# core_pwr.net
KiCad netlist of a schematic drawn in Altium Designer
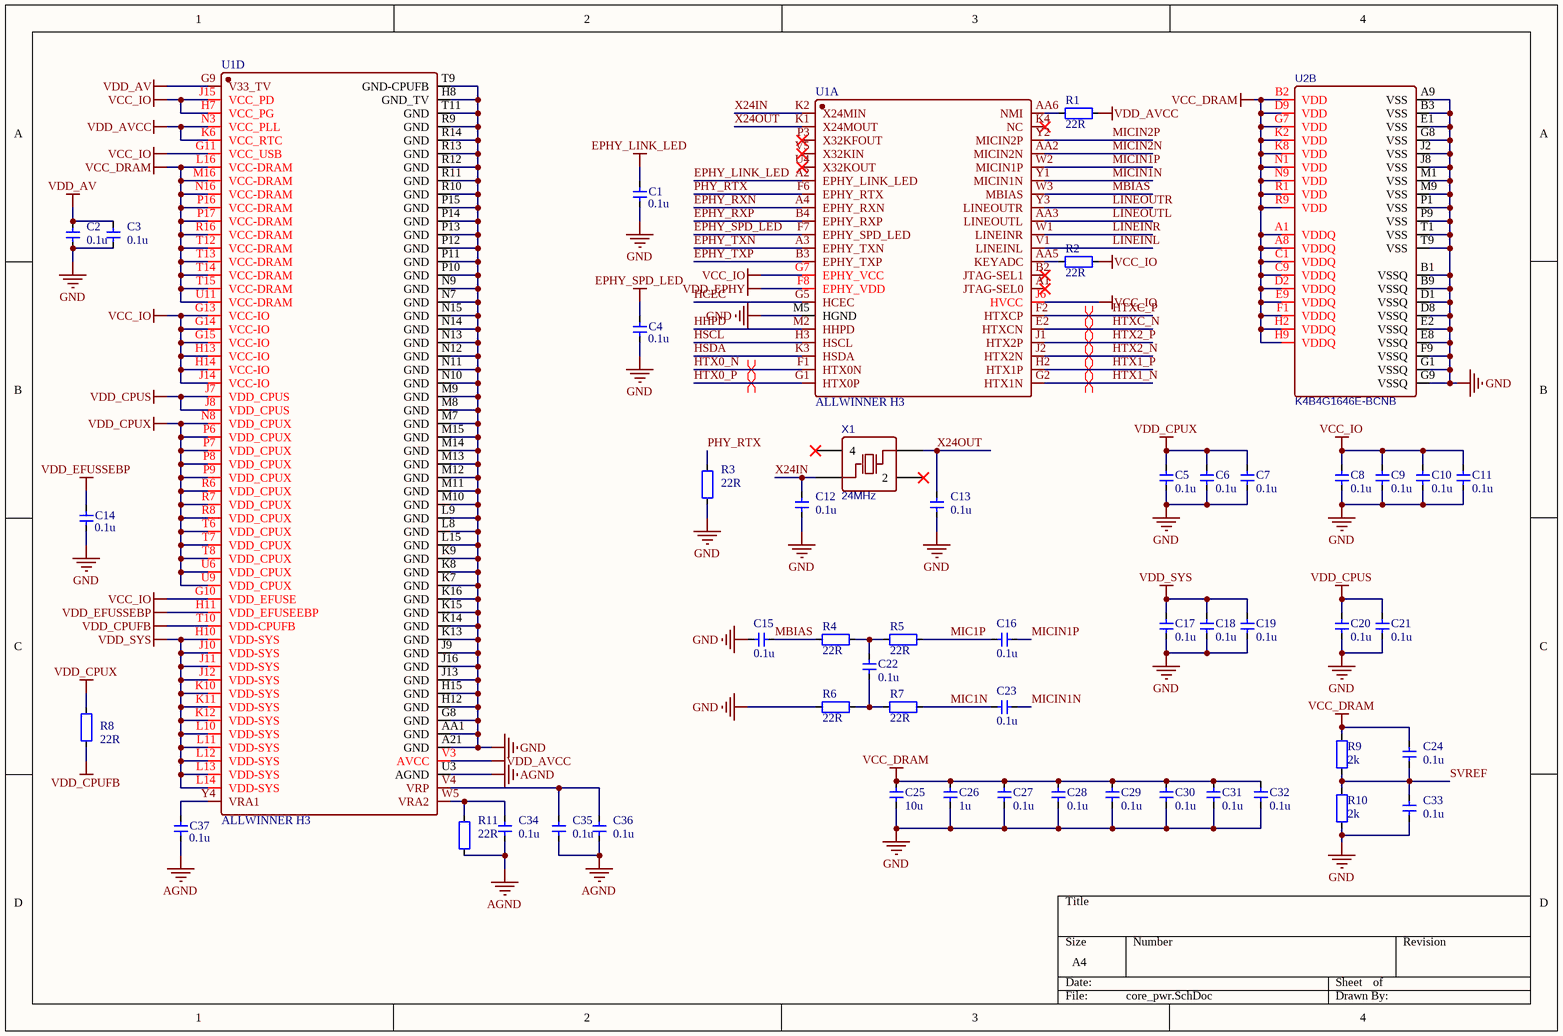
[diagram p0: core_pwr.SchDoc]

(export (version "E")
  (design (tool "Eeschema 10.0.6"))
  (components
    (comp (ref "C1")
      (value "0.1u")
      (footprint "C0402")
      (description "Capacitor")
      (fields (field (name "Comment") "CAP-0402"))
      (libsource (lib "core") (part "CAP-0402"))
    )
    (comp (ref "C2")
      (value "0.1u")
      (footprint "C0402")
      (description "Capacitor")
      (fields (field (name "Comment") "CAP-0402"))
      (libsource (lib "core") (part "CAP-0402"))
    )
    (comp (ref "C3")
      (value "0.1u")
      (footprint "C0402")
      (description "Capacitor")
      (fields (field (name "Comment") "CAP-0402"))
      (libsource (lib "core") (part "CAP-0402"))
    )
    (comp (ref "C4")
      (value "0.1u")
      (footprint "C0402")
      (description "Capacitor")
      (fields (field (name "Comment") "CAP-0402"))
      (libsource (lib "core") (part "CAP-0402"))
    )
    (comp (ref "C5")
      (value "0.1u")
      (footprint "C0402")
      (description "Capacitor")
      (fields (field (name "Comment") "CAP-0402"))
      (libsource (lib "core") (part "CAP-0402"))
    )
    (comp (ref "C6")
      (value "0.1u")
      (footprint "C0402")
      (description "Capacitor")
      (fields (field (name "Comment") "CAP-0402"))
      (libsource (lib "core") (part "CAP-0402"))
    )
    (comp (ref "C7")
      (value "0.1u")
      (footprint "C0402")
      (description "Capacitor")
      (fields (field (name "Comment") "CAP-0402"))
      (libsource (lib "core") (part "CAP-0402"))
    )
    (comp (ref "C8")
      (value "0.1u")
      (footprint "C0402")
      (description "Capacitor")
      (fields (field (name "Comment") "CAP-0402"))
      (libsource (lib "core") (part "CAP-0402"))
    )
    (comp (ref "C9")
      (value "0.1u")
      (footprint "C0402")
      (description "Capacitor")
      (fields (field (name "Comment") "CAP-0402"))
      (libsource (lib "core") (part "CAP-0402"))
    )
    (comp (ref "C10")
      (value "0.1u")
      (footprint "C0402")
      (description "Capacitor")
      (fields (field (name "Comment") "CAP-0402"))
      (libsource (lib "core") (part "CAP-0402"))
    )
    (comp (ref "C11")
      (value "0.1u")
      (footprint "C0402")
      (description "Capacitor")
      (fields (field (name "Comment") "CAP-0402"))
      (libsource (lib "core") (part "CAP-0402"))
    )
    (comp (ref "C12")
      (value "0.1u")
      (footprint "C0402")
      (description "Capacitor")
      (fields (field (name "Comment") "CAP-0402"))
      (libsource (lib "core") (part "CAP-0402"))
    )
    (comp (ref "C13")
      (value "0.1u")
      (footprint "C0402")
      (description "Capacitor")
      (fields (field (name "Comment") "CAP-0402"))
      (libsource (lib "core") (part "CAP-0402"))
    )
    (comp (ref "C14")
      (value "0.1u")
      (footprint "C0402")
      (description "Capacitor")
      (fields (field (name "Comment") "CAP-0402"))
      (libsource (lib "core") (part "CAP-0402"))
    )
    (comp (ref "C15")
      (value "0.1u")
      (footprint "C0402")
      (description "Capacitor")
      (fields (field (name "Comment") "CAP-0402"))
      (libsource (lib "core") (part "CAP-0402"))
    )
    (comp (ref "C16")
      (value "0.1u")
      (footprint "C0402")
      (description "Capacitor")
      (fields (field (name "Comment") "CAP-0402"))
      (libsource (lib "core") (part "CAP-0402"))
    )
    (comp (ref "C17")
      (value "0.1u")
      (footprint "C0402")
      (description "Capacitor")
      (fields (field (name "Comment") "CAP-0402"))
      (libsource (lib "core") (part "CAP-0402"))
    )
    (comp (ref "C18")
      (value "0.1u")
      (footprint "C0402")
      (description "Capacitor")
      (fields (field (name "Comment") "CAP-0402"))
      (libsource (lib "core") (part "CAP-0402"))
    )
    (comp (ref "C19")
      (value "0.1u")
      (footprint "C0402")
      (description "Capacitor")
      (fields (field (name "Comment") "CAP-0402"))
      (libsource (lib "core") (part "CAP-0402"))
    )
    (comp (ref "C20")
      (value "0.1u")
      (footprint "C0402")
      (description "Capacitor")
      (fields (field (name "Comment") "CAP-0402"))
      (libsource (lib "core") (part "CAP-0402"))
    )
    (comp (ref "C21")
      (value "0.1u")
      (footprint "C0402")
      (description "Capacitor")
      (fields (field (name "Comment") "CAP-0402"))
      (libsource (lib "core") (part "CAP-0402"))
    )
    (comp (ref "C22")
      (value "0.1u")
      (footprint "C0402")
      (description "Capacitor")
      (fields (field (name "Comment") "CAP-0402"))
      (libsource (lib "core") (part "CAP-0402"))
    )
    (comp (ref "C23")
      (value "0.1u")
      (footprint "C0402")
      (description "Capacitor")
      (fields (field (name "Comment") "CAP-0402"))
      (libsource (lib "core") (part "CAP-0402"))
    )
    (comp (ref "C24")
      (value "0.1u")
      (footprint "C0402")
      (description "Capacitor")
      (fields (field (name "Comment") "CAP-0402"))
      (libsource (lib "core") (part "CAP-0402"))
    )
    (comp (ref "C25")
      (value "10u")
      (footprint "C0402")
      (description "Capacitor")
      (fields (field (name "Comment") "CAP-0402"))
      (libsource (lib "core") (part "CAP-0402"))
    )
    (comp (ref "C26")
      (value "1u")
      (footprint "C0402")
      (description "Capacitor")
      (fields (field (name "Comment") "CAP-0402"))
      (libsource (lib "core") (part "CAP-0402"))
    )
    (comp (ref "C27")
      (value "0.1u")
      (footprint "C0402")
      (description "Capacitor")
      (fields (field (name "Comment") "CAP-0402"))
      (libsource (lib "core") (part "CAP-0402"))
    )
    (comp (ref "C28")
      (value "0.1u")
      (footprint "C0402")
      (description "Capacitor")
      (fields (field (name "Comment") "CAP-0402"))
      (libsource (lib "core") (part "CAP-0402"))
    )
    (comp (ref "C29")
      (value "0.1u")
      (footprint "C0402")
      (description "Capacitor")
      (fields (field (name "Comment") "CAP-0402"))
      (libsource (lib "core") (part "CAP-0402"))
    )
    (comp (ref "C30")
      (value "0.1u")
      (footprint "C0402")
      (description "Capacitor")
      (fields (field (name "Comment") "CAP-0402"))
      (libsource (lib "core") (part "CAP-0402"))
    )
    (comp (ref "C31")
      (value "0.1u")
      (footprint "C0402")
      (description "Capacitor")
      (fields (field (name "Comment") "CAP-0402"))
      (libsource (lib "core") (part "CAP-0402"))
    )
    (comp (ref "C32")
      (value "0.1u")
      (footprint "C0402")
      (description "Capacitor")
      (fields (field (name "Comment") "CAP-0402"))
      (libsource (lib "core") (part "CAP-0402"))
    )
    (comp (ref "C33")
      (value "0.1u")
      (footprint "C0402")
      (description "Capacitor")
      (fields (field (name "Comment") "CAP-0402"))
      (libsource (lib "core") (part "CAP-0402"))
    )
    (comp (ref "C34")
      (value "0.1u")
      (footprint "C0402")
      (description "Capacitor")
      (fields (field (name "Comment") "CAP-0402"))
      (libsource (lib "core") (part "CAP-0402"))
    )
    (comp (ref "C35")
      (value "0.1u")
      (footprint "C0402")
      (description "Capacitor")
      (fields (field (name "Comment") "CAP-0402"))
      (libsource (lib "core") (part "CAP-0402"))
    )
    (comp (ref "C36")
      (value "0.1u")
      (footprint "C0402")
      (description "Capacitor")
      (fields (field (name "Comment") "CAP-0402"))
      (libsource (lib "core") (part "CAP-0402"))
    )
    (comp (ref "C37")
      (value "0.1u")
      (footprint "C0402")
      (description "Capacitor")
      (fields (field (name "Comment") "CAP-0402"))
      (libsource (lib "core") (part "CAP-0402"))
    )
    (comp (ref "R1")
      (value "22R")
      (footprint "R0402")
      (description "Resistor")
      (fields (field (name "Comment") "RES-0402"))
      (libsource (lib "") (part "RES-0402_1"))
    )
    (comp (ref "R2")
      (value "22R")
      (footprint "R0402")
      (description "Resistor")
      (fields (field (name "Comment") "RES-0402"))
      (libsource (lib "") (part "RES-0402_1"))
    )
    (comp (ref "R3")
      (value "22R")
      (footprint "R0402")
      (description "Resistor")
      (fields (field (name "Comment") "RES-0402"))
      (libsource (lib "core") (part "RES-0402"))
    )
    (comp (ref "R4")
      (value "22R")
      (footprint "R0402")
      (description "Resistor")
      (fields (field (name "Comment") "RES-0402"))
      (libsource (lib "") (part "RES-0402_1"))
    )
    (comp (ref "R5")
      (value "22R")
      (footprint "R0402")
      (description "Resistor")
      (fields (field (name "Comment") "RES-0402"))
      (libsource (lib "") (part "RES-0402_1"))
    )
    (comp (ref "R6")
      (value "22R")
      (footprint "R0402")
      (description "Resistor")
      (fields (field (name "Comment") "RES-0402"))
      (libsource (lib "") (part "RES-0402_1"))
    )
    (comp (ref "R7")
      (value "22R")
      (footprint "R0402")
      (description "Resistor")
      (fields (field (name "Comment") "RES-0402"))
      (libsource (lib "") (part "RES-0402_3"))
    )
    (comp (ref "R8")
      (value "22R")
      (footprint "R0402")
      (description "Resistor")
      (fields (field (name "Comment") "RES-0402"))
      (libsource (lib "core") (part "RES-0402"))
    )
    (comp (ref "R9")
      (value "2k")
      (footprint "R0402")
      (description "Resistor")
      (fields (field (name "Comment") "RES-0402"))
      (libsource (lib "") (part "RES-0402_2"))
    )
    (comp (ref "R10")
      (value "2k")
      (footprint "R0402")
      (description "Resistor")
      (fields (field (name "Comment") "RES-0402"))
      (libsource (lib "") (part "RES-0402_2"))
    )
    (comp (ref "R11")
      (value "22R")
      (footprint "R0402")
      (description "Resistor")
      (fields (field (name "Comment") "RES-0402"))
      (libsource (lib "core") (part "RES-0402"))
    )
    (comp (ref "U1")
      (value "ALLWINNER H3")
      (footprint "BGA-347_L14.0-W14.0-R21-C21-P0.65-TL")
      (libsource (lib "core") (part "allwinner H3"))
    )
    (comp (ref "U2")
      (value "K4B4G1646E-BCNB")
      (footprint "FBGA-96_L13.5-W7.5-R16-C6-P0.80-TL")
      (fields (field (name "BOM_SUPPLIER PART") "C2803248") (field (name "CONTRIBUTOR") "LCSC"))
      (libsource (lib "core") (part "K4B4G1646E-BCNB"))
    )
    (comp (ref "X1")
      (value "24MHz")
      (footprint "OSC-SMD_4P-L3.2-W2.5-BL")
      (fields
        (field (name "BOM_MANUFACTURER PART") "DSX321G 24MHz")
        (field (name "BOM_SUPPLIER PART") "C93235")
        (field (name "CONTRIBUTOR") "LCSC")
      )
      (libsource (lib "core") (part "24MHz"))
    )
  )
  (nets
    (net (code "1") (name "/EPHY_RXN") (class "Default")
      (node (ref "U1") (pin "A4") (pinfunction "EPHY_RXN_A4") (pintype "passive"))
    )
    (net (code "2") (name "/EPHY_RXP") (class "Default")
      (node (ref "U1") (pin "B4") (pinfunction "EPHY_RXP_B4") (pintype "passive"))
    )
    (net (code "3") (name "/EPHY_TXN") (class "Default")
      (node (ref "U1") (pin "A3") (pinfunction "EPHY_TXN_A3") (pintype "passive"))
    )
    (net (code "4") (name "/EPHY_TXP") (class "Default")
      (node (ref "U1") (pin "B3") (pinfunction "EPHY_TXP_B3") (pintype "passive"))
    )
    (net (code "5") (name "/HCEC") (class "Default")
      (node (ref "U1") (pin "G5") (pinfunction "HCEC_G5") (pintype "passive"))
    )
    (net (code "6") (name "/HHPD") (class "Default")
      (node (ref "U1") (pin "M2") (pinfunction "HHPD_M2") (pintype "passive"))
    )
    (net (code "7") (name "/HSCL") (class "Default")
      (node (ref "U1") (pin "H3") (pinfunction "HSCL_H3") (pintype "passive"))
    )
    (net (code "8") (name "/HSDA") (class "Default")
      (node (ref "U1") (pin "K3") (pinfunction "HSDA_K3") (pintype "passive"))
    )
    (net (code "9") (name "/HTX0_N") (class "Default")
      (node (ref "U1") (pin "F1") (pinfunction "HTX0N_F1") (pintype "passive"))
    )
    (net (code "10") (name "/HTX0_P") (class "Default")
      (node (ref "U1") (pin "G1") (pinfunction "HTX0P_G1") (pintype "passive"))
    )
    (net (code "11") (name "/HTX1_N") (class "Default")
      (node (ref "U1") (pin "G2") (pinfunction "HTX1N_G2") (pintype "passive"))
    )
    (net (code "12") (name "/HTX1_P") (class "Default")
      (node (ref "U1") (pin "H2") (pinfunction "HTX1P_H2") (pintype "passive"))
    )
    (net (code "13") (name "/HTX2_N") (class "Default")
      (node (ref "U1") (pin "J2") (pinfunction "HTX2N_J2") (pintype "passive"))
    )
    (net (code "14") (name "/HTX2_P") (class "Default")
      (node (ref "U1") (pin "J1") (pinfunction "HTX2P_J1") (pintype "passive"))
    )
    (net (code "15") (name "/HTXC_N") (class "Default")
      (node (ref "U1") (pin "E2") (pinfunction "HTXCN_E2") (pintype "passive"))
    )
    (net (code "16") (name "/HTXC_P") (class "Default")
      (node (ref "U1") (pin "F2") (pinfunction "HTXCP_F2") (pintype "passive"))
    )
    (net (code "17") (name "/LINEINL") (class "Default")
      (node (ref "U1") (pin "V1") (pinfunction "LINEINL_V1") (pintype "passive"))
    )
    (net (code "18") (name "/LINEINR") (class "Default")
      (node (ref "U1") (pin "W1") (pinfunction "LINEINR_W1") (pintype "passive"))
    )
    (net (code "19") (name "/LINEOUTL") (class "Default")
      (node (ref "U1") (pin "AA3") (pinfunction "LINEOUTL_AA3") (pintype "passive"))
    )
    (net (code "20") (name "/LINEOUTR") (class "Default")
      (node (ref "U1") (pin "Y3") (pinfunction "LINEOUTR_Y3") (pintype "passive"))
    )
    (net (code "21") (name "/MBIAS") (class "Default")
      (node (ref "C15") (pin "1") (pinfunction "1_1") (pintype "passive"))
      (node (ref "R4") (pin "2") (pinfunction "2_2") (pintype "passive"))
      (node (ref "U1") (pin "W3") (pinfunction "MBIAS_W3") (pintype "passive"))
    )
    (net (code "22") (name "/MIC1N") (class "Default")
      (node (ref "C23") (pin "1") (pinfunction "1_1") (pintype "passive"))
      (node (ref "R7") (pin "2") (pinfunction "2_2") (pintype "passive"))
    )
    (net (code "23") (name "/MIC1P") (class "Default")
      (node (ref "C16") (pin "2") (pinfunction "2_2") (pintype "passive"))
      (node (ref "R5") (pin "1") (pinfunction "1_1") (pintype "passive"))
    )
    (net (code "24") (name "/MICIN1N") (class "Default")
      (node (ref "C23") (pin "2") (pinfunction "2_2") (pintype "passive"))
      (node (ref "U1") (pin "Y1") (pinfunction "MICIN1N_Y1") (pintype "passive"))
    )
    (net (code "25") (name "/MICIN1P") (class "Default")
      (node (ref "C16") (pin "1") (pinfunction "1_1") (pintype "passive"))
      (node (ref "U1") (pin "W2") (pinfunction "MICIN1P_W2") (pintype "passive"))
    )
    (net (code "26") (name "/MICIN2N") (class "Default")
      (node (ref "U1") (pin "AA2") (pinfunction "MICIN2N_AA2") (pintype "passive"))
    )
    (net (code "27") (name "/MICIN2P") (class "Default")
      (node (ref "U1") (pin "Y2") (pinfunction "MICIN2P_Y2") (pintype "passive"))
    )
    (net (code "28") (name "/PHY_RTX") (class "Default")
      (node (ref "R3") (pin "2") (pinfunction "2_2") (pintype "passive"))
      (node (ref "U1") (pin "F6") (pinfunction "EPHY_RTX_F6") (pintype "passive"))
    )
    (net (code "29") (name "/SVREF") (class "Default")
      (node (ref "C24") (pin "1") (pinfunction "1_1") (pintype "passive"))
      (node (ref "C33") (pin "2") (pinfunction "2_2") (pintype "passive"))
      (node (ref "R10") (pin "1") (pinfunction "1_1") (pintype "passive"))
      (node (ref "R9") (pin "2") (pinfunction "2_2") (pintype "passive"))
    )
    (net (code "30") (name "/X24IN") (class "Default")
      (node (ref "C12") (pin "2") (pinfunction "2_2") (pintype "passive"))
      (node (ref "U1") (pin "K2") (pinfunction "X24MIN_K2") (pintype "passive"))
      (node (ref "X1") (pin "1") (pinfunction "OSC1_1") (pintype "passive"))
    )
    (net (code "31") (name "/X24OUT") (class "Default")
      (node (ref "C13") (pin "2") (pinfunction "2_2") (pintype "passive"))
      (node (ref "U1") (pin "K1") (pinfunction "X24MOUT_K1") (pintype "passive"))
      (node (ref "X1") (pin "3") (pinfunction "OSC2_3") (pintype "passive"))
    )
    (net (code "32") (name "AGND") (class "Default")
      (node (ref "C34") (pin "1") (pinfunction "1_1") (pintype "passive"))
      (node (ref "C35") (pin "1") (pinfunction "1_1") (pintype "passive"))
      (node (ref "C36") (pin "1") (pinfunction "1_1") (pintype "passive"))
      (node (ref "C37") (pin "1") (pinfunction "1_1") (pintype "passive"))
      (node (ref "R11") (pin "1") (pinfunction "1_1") (pintype "passive"))
      (node (ref "U1") (pin "U3") (pinfunction "AGND_U3") (pintype "passive"))
    )
    (net (code "33") (name "EPHY_LINK_LED") (class "Default")
      (node (ref "C1") (pin "2") (pinfunction "2_2") (pintype "passive"))
      (node (ref "U1") (pin "A2") (pinfunction "EPHY_LINK_LED_A2") (pintype "passive"))
    )
    (net (code "34") (name "EPHY_SPD_LED") (class "Default")
      (node (ref "C4") (pin "2") (pinfunction "2_2") (pintype "passive"))
      (node (ref "U1") (pin "F7") (pinfunction "EPHY_SPD_LED_F7") (pintype "passive"))
    )
    (net (code "35") (name "GND") (class "Default")
      (node (ref "C1") (pin "1") (pinfunction "1_1") (pintype "passive"))
      (node (ref "C10") (pin "2") (pinfunction "2_2") (pintype "passive"))
      (node (ref "C11") (pin "2") (pinfunction "2_2") (pintype "passive"))
      (node (ref "C12") (pin "1") (pinfunction "1_1") (pintype "passive"))
      (node (ref "C13") (pin "1") (pinfunction "1_1") (pintype "passive"))
      (node (ref "C14") (pin "1") (pinfunction "1_1") (pintype "passive"))
      (node (ref "C15") (pin "2") (pinfunction "2_2") (pintype "passive"))
      (node (ref "C17") (pin "2") (pinfunction "2_2") (pintype "passive"))
      (node (ref "C18") (pin "2") (pinfunction "2_2") (pintype "passive"))
      (node (ref "C19") (pin "2") (pinfunction "2_2") (pintype "passive"))
      (node (ref "C2") (pin "1") (pinfunction "1_1") (pintype "passive"))
      (node (ref "C20") (pin "2") (pinfunction "2_2") (pintype "passive"))
      (node (ref "C21") (pin "2") (pinfunction "2_2") (pintype "passive"))
      (node (ref "C25") (pin "2") (pinfunction "2_2") (pintype "passive"))
      (node (ref "C26") (pin "2") (pinfunction "2_2") (pintype "passive"))
      (node (ref "C27") (pin "2") (pinfunction "2_2") (pintype "passive"))
      (node (ref "C28") (pin "2") (pinfunction "2_2") (pintype "passive"))
      (node (ref "C29") (pin "2") (pinfunction "2_2") (pintype "passive"))
      (node (ref "C3") (pin "1") (pinfunction "1_1") (pintype "passive"))
      (node (ref "C30") (pin "2") (pinfunction "2_2") (pintype "passive"))
      (node (ref "C31") (pin "2") (pinfunction "2_2") (pintype "passive"))
      (node (ref "C32") (pin "2") (pinfunction "2_2") (pintype "passive"))
      (node (ref "C33") (pin "1") (pinfunction "1_1") (pintype "passive"))
      (node (ref "C4") (pin "1") (pinfunction "1_1") (pintype "passive"))
      (node (ref "C5") (pin "2") (pinfunction "2_2") (pintype "passive"))
      (node (ref "C6") (pin "2") (pinfunction "2_2") (pintype "passive"))
      (node (ref "C7") (pin "2") (pinfunction "2_2") (pintype "passive"))
      (node (ref "C8") (pin "2") (pinfunction "2_2") (pintype "passive"))
      (node (ref "C9") (pin "2") (pinfunction "2_2") (pintype "passive"))
      (node (ref "R10") (pin "2") (pinfunction "2_2") (pintype "passive"))
      (node (ref "R3") (pin "1") (pinfunction "1_1") (pintype "passive"))
      (node (ref "R6") (pin "2") (pinfunction "2_2") (pintype "passive"))
      (node (ref "U1") (pin "A21") (pinfunction "GND_A21") (pintype "passive"))
      (node (ref "U1") (pin "AA1") (pinfunction "GND_AA1") (pintype "passive"))
      (node (ref "U1") (pin "G8") (pinfunction "GND_G8") (pintype "passive"))
      (node (ref "U1") (pin "H12") (pinfunction "GND_H12") (pintype "passive"))
      (node (ref "U1") (pin "H15") (pinfunction "GND_H15") (pintype "passive"))
      (node (ref "U1") (pin "H8") (pinfunction "GND_TV_H8") (pintype "passive"))
      (node (ref "U1") (pin "J13") (pinfunction "GND_J13") (pintype "passive"))
      (node (ref "U1") (pin "J16") (pinfunction "GND_J16") (pintype "passive"))
      (node (ref "U1") (pin "J9") (pinfunction "GND_J9") (pintype "passive"))
      (node (ref "U1") (pin "K13") (pinfunction "GND_K13") (pintype "passive"))
      (node (ref "U1") (pin "K14") (pinfunction "GND_K14") (pintype "passive"))
      (node (ref "U1") (pin "K15") (pinfunction "GND_K15") (pintype "passive"))
      (node (ref "U1") (pin "K16") (pinfunction "GND_K16") (pintype "passive"))
      (node (ref "U1") (pin "K7") (pinfunction "GND_K7") (pintype "passive"))
      (node (ref "U1") (pin "K8") (pinfunction "GND_K8") (pintype "passive"))
      (node (ref "U1") (pin "K9") (pinfunction "GND_K9") (pintype "passive"))
      (node (ref "U1") (pin "L15") (pinfunction "GND_L15") (pintype "passive"))
      (node (ref "U1") (pin "L8") (pinfunction "GND_L8") (pintype "passive"))
      (node (ref "U1") (pin "L9") (pinfunction "GND_L9") (pintype "passive"))
      (node (ref "U1") (pin "M10") (pinfunction "GND_M10") (pintype "passive"))
      (node (ref "U1") (pin "M11") (pinfunction "GND_M11") (pintype "passive"))
      (node (ref "U1") (pin "M12") (pinfunction "GND_M12") (pintype "passive"))
      (node (ref "U1") (pin "M13") (pinfunction "GND_M13") (pintype "passive"))
      (node (ref "U1") (pin "M14") (pinfunction "GND_M14") (pintype "passive"))
      (node (ref "U1") (pin "M15") (pinfunction "GND_M15") (pintype "passive"))
      (node (ref "U1") (pin "M5") (pinfunction "HGND_M5") (pintype "passive"))
      (node (ref "U1") (pin "M7") (pinfunction "GND_M7") (pintype "passive"))
      (node (ref "U1") (pin "M8") (pinfunction "GND_M8") (pintype "passive"))
      (node (ref "U1") (pin "M9") (pinfunction "GND_M9") (pintype "passive"))
      (node (ref "U1") (pin "N10") (pinfunction "GND_N10") (pintype "passive"))
      (node (ref "U1") (pin "N11") (pinfunction "GND_N11") (pintype "passive"))
      (node (ref "U1") (pin "N12") (pinfunction "GND_N12") (pintype "passive"))
      (node (ref "U1") (pin "N13") (pinfunction "GND_N13") (pintype "passive"))
      (node (ref "U1") (pin "N14") (pinfunction "GND_N14") (pintype "passive"))
      (node (ref "U1") (pin "N15") (pinfunction "GND_N15") (pintype "passive"))
      (node (ref "U1") (pin "N7") (pinfunction "GND_N7") (pintype "passive"))
      (node (ref "U1") (pin "N9") (pinfunction "GND_N9") (pintype "passive"))
      (node (ref "U1") (pin "P10") (pinfunction "GND_P10") (pintype "passive"))
      (node (ref "U1") (pin "P11") (pinfunction "GND_P11") (pintype "passive"))
      (node (ref "U1") (pin "P12") (pinfunction "GND_P12") (pintype "passive"))
      (node (ref "U1") (pin "P13") (pinfunction "GND_P13") (pintype "passive"))
      (node (ref "U1") (pin "P14") (pinfunction "GND_P14") (pintype "passive"))
      (node (ref "U1") (pin "P15") (pinfunction "GND_P15") (pintype "passive"))
      (node (ref "U1") (pin "R10") (pinfunction "GND_R10") (pintype "passive"))
      (node (ref "U1") (pin "R11") (pinfunction "GND_R11") (pintype "passive"))
      (node (ref "U1") (pin "R12") (pinfunction "GND_R12") (pintype "passive"))
      (node (ref "U1") (pin "R13") (pinfunction "GND_R13") (pintype "passive"))
      (node (ref "U1") (pin "R14") (pinfunction "GND_R14") (pintype "passive"))
      (node (ref "U1") (pin "R9") (pinfunction "GND_R9") (pintype "passive"))
      (node (ref "U1") (pin "T11") (pinfunction "GND_T11") (pintype "passive"))
      (node (ref "U1") (pin "T9") (pinfunction "GND-CPUFB_T9") (pintype "passive"))
      (node (ref "U2") (pin "A9") (pinfunction "VSS_A9") (pintype "passive"))
      (node (ref "U2") (pin "B1") (pinfunction "VSSQ_B1") (pintype "passive"))
      (node (ref "U2") (pin "B3") (pinfunction "VSS_B3") (pintype "passive"))
      (node (ref "U2") (pin "B9") (pinfunction "VSSQ_B9") (pintype "passive"))
      (node (ref "U2") (pin "D1") (pinfunction "VSSQ_D1") (pintype "passive"))
      (node (ref "U2") (pin "D8") (pinfunction "VSSQ_D8") (pintype "passive"))
      (node (ref "U2") (pin "E1") (pinfunction "VSS_E1") (pintype "passive"))
      (node (ref "U2") (pin "E2") (pinfunction "VSSQ_E2") (pintype "passive"))
      (node (ref "U2") (pin "E8") (pinfunction "VSSQ_E8") (pintype "passive"))
      (node (ref "U2") (pin "F9") (pinfunction "VSSQ_F9") (pintype "passive"))
      (node (ref "U2") (pin "G1") (pinfunction "VSSQ_G1") (pintype "passive"))
      (node (ref "U2") (pin "G8") (pinfunction "VSS_G8") (pintype "passive"))
      (node (ref "U2") (pin "G9") (pinfunction "VSSQ_G9") (pintype "passive"))
      (node (ref "U2") (pin "J2") (pinfunction "VSS_J2") (pintype "passive"))
      (node (ref "U2") (pin "J8") (pinfunction "VSS_J8") (pintype "passive"))
      (node (ref "U2") (pin "M1") (pinfunction "VSS_M1") (pintype "passive"))
      (node (ref "U2") (pin "M9") (pinfunction "VSS_M9") (pintype "passive"))
      (node (ref "U2") (pin "P1") (pinfunction "VSS_P1") (pintype "passive"))
      (node (ref "U2") (pin "P9") (pinfunction "VSS_P9") (pintype "passive"))
      (node (ref "U2") (pin "T1") (pinfunction "VSS_T1") (pintype "passive"))
      (node (ref "U2") (pin "T9") (pinfunction "VSS_T9") (pintype "passive"))
    )
    (net (code "36") (name "Net-(C22-Pad1)") (class "Default")
      (node (ref "C22") (pin "1") (pinfunction "1_1") (pintype "passive"))
      (node (ref "R4") (pin "1") (pinfunction "1_1") (pintype "passive"))
      (node (ref "R5") (pin "2") (pinfunction "2_2") (pintype "passive"))
    )
    (net (code "37") (name "Net-(C22-Pad2)") (class "Default")
      (node (ref "C22") (pin "2") (pinfunction "2_2") (pintype "passive"))
      (node (ref "R6") (pin "1") (pinfunction "1_1") (pintype "passive"))
      (node (ref "R7") (pin "1") (pinfunction "1_1") (pintype "passive"))
    )
    (net (code "38") (name "Net-(U1A-KEYADC)") (class "Default")
      (node (ref "R2") (pin "2") (pinfunction "2_2") (pintype "passive"))
      (node (ref "U1") (pin "AA5") (pinfunction "KEYADC_AA5") (pintype "passive"))
    )
    (net (code "39") (name "Net-(U1A-NMI)") (class "Default")
      (node (ref "R1") (pin "2") (pinfunction "2_2") (pintype "passive"))
      (node (ref "U1") (pin "AA6") (pinfunction "NMI_AA6") (pintype "passive"))
    )
    (net (code "40") (name "Net-(U1D-VRA1)") (class "Default")
      (node (ref "C37") (pin "2") (pinfunction "2_2") (pintype "passive"))
      (node (ref "U1") (pin "Y4") (pinfunction "VRA1_Y4") (pintype "passive"))
    )
    (net (code "41") (name "Net-(U1D-VRA2)") (class "Default")
      (node (ref "C34") (pin "2") (pinfunction "2_2") (pintype "passive"))
      (node (ref "R11") (pin "2") (pinfunction "2_2") (pintype "passive"))
      (node (ref "U1") (pin "W5") (pinfunction "VRA2_W5") (pintype "passive"))
    )
    (net (code "42") (name "Net-(U1D-VRP)") (class "Default")
      (node (ref "C35") (pin "2") (pinfunction "2_2") (pintype "passive"))
      (node (ref "C36") (pin "2") (pinfunction "2_2") (pintype "passive"))
      (node (ref "U1") (pin "V4") (pinfunction "VRP_V4") (pintype "passive"))
    )
    (net (code "43") (name "VCC_DRAM") (class "Default")
      (node (ref "C24") (pin "2") (pinfunction "2_2") (pintype "passive"))
      (node (ref "C25") (pin "1") (pinfunction "1_1") (pintype "passive"))
      (node (ref "C26") (pin "1") (pinfunction "1_1") (pintype "passive"))
      (node (ref "C27") (pin "1") (pinfunction "1_1") (pintype "passive"))
      (node (ref "C28") (pin "1") (pinfunction "1_1") (pintype "passive"))
      (node (ref "C29") (pin "1") (pinfunction "1_1") (pintype "passive"))
      (node (ref "C30") (pin "1") (pinfunction "1_1") (pintype "passive"))
      (node (ref "C31") (pin "1") (pinfunction "1_1") (pintype "passive"))
      (node (ref "C32") (pin "1") (pinfunction "1_1") (pintype "passive"))
      (node (ref "R9") (pin "1") (pinfunction "1_1") (pintype "passive"))
      (node (ref "U1") (pin "L16") (pinfunction "VCC-DRAM_L16") (pintype "passive"))
      (node (ref "U1") (pin "M16") (pinfunction "VCC-DRAM_M16") (pintype "passive"))
      (node (ref "U1") (pin "N16") (pinfunction "VCC-DRAM_N16") (pintype "passive"))
      (node (ref "U1") (pin "P16") (pinfunction "VCC-DRAM_P16") (pintype "passive"))
      (node (ref "U1") (pin "P17") (pinfunction "VCC-DRAM_P17") (pintype "passive"))
      (node (ref "U1") (pin "R16") (pinfunction "VCC-DRAM_R16") (pintype "passive"))
      (node (ref "U1") (pin "T12") (pinfunction "VCC-DRAM_T12") (pintype "passive"))
      (node (ref "U1") (pin "T13") (pinfunction "VCC-DRAM_T13") (pintype "passive"))
      (node (ref "U1") (pin "T14") (pinfunction "VCC-DRAM_T14") (pintype "passive"))
      (node (ref "U1") (pin "T15") (pinfunction "VCC-DRAM_T15") (pintype "passive"))
      (node (ref "U1") (pin "U11") (pinfunction "VCC-DRAM_U11") (pintype "passive"))
      (node (ref "U2") (pin "A1") (pinfunction "VDDQ_A1") (pintype "passive"))
      (node (ref "U2") (pin "A8") (pinfunction "VDDQ_A8") (pintype "passive"))
      (node (ref "U2") (pin "B2") (pinfunction "VDD_B2") (pintype "passive"))
      (node (ref "U2") (pin "C1") (pinfunction "VDDQ_C1") (pintype "passive"))
      (node (ref "U2") (pin "C9") (pinfunction "VDDQ_C9") (pintype "passive"))
      (node (ref "U2") (pin "D2") (pinfunction "VDDQ_D2") (pintype "passive"))
      (node (ref "U2") (pin "D9") (pinfunction "VDD_D9") (pintype "passive"))
      (node (ref "U2") (pin "E9") (pinfunction "VDDQ_E9") (pintype "passive"))
      (node (ref "U2") (pin "F1") (pinfunction "VDDQ_F1") (pintype "passive"))
      (node (ref "U2") (pin "G7") (pinfunction "VDD_G7") (pintype "passive"))
      (node (ref "U2") (pin "H2") (pinfunction "VDDQ_H2") (pintype "passive"))
      (node (ref "U2") (pin "H9") (pinfunction "VDDQ_H9") (pintype "passive"))
      (node (ref "U2") (pin "K2") (pinfunction "VDD_K2") (pintype "passive"))
      (node (ref "U2") (pin "K8") (pinfunction "VDD_K8") (pintype "passive"))
      (node (ref "U2") (pin "N1") (pinfunction "VDD_N1") (pintype "passive"))
      (node (ref "U2") (pin "N9") (pinfunction "VDD_N9") (pintype "passive"))
      (node (ref "U2") (pin "R1") (pinfunction "VDD_R1") (pintype "passive"))
      (node (ref "U2") (pin "R9") (pinfunction "VDD_R9") (pintype "passive"))
    )
    (net (code "44") (name "VCC_IO") (class "Default")
      (node (ref "C10") (pin "1") (pinfunction "1_1") (pintype "passive"))
      (node (ref "C11") (pin "1") (pinfunction "1_1") (pintype "passive"))
      (node (ref "C8") (pin "1") (pinfunction "1_1") (pintype "passive"))
      (node (ref "C9") (pin "1") (pinfunction "1_1") (pintype "passive"))
      (node (ref "R2") (pin "1") (pinfunction "1_1") (pintype "passive"))
      (node (ref "U1") (pin "G10") (pinfunction "VDD_EFUSE_G10") (pintype "passive"))
      (node (ref "U1") (pin "G11") (pinfunction "VCC_USB_G11") (pintype "passive"))
      (node (ref "U1") (pin "G13") (pinfunction "VCC-IO_G13") (pintype "passive"))
      (node (ref "U1") (pin "G14") (pinfunction "VCC-IO_G14") (pintype "passive"))
      (node (ref "U1") (pin "G15") (pinfunction "VCC-IO_G15") (pintype "passive"))
      (node (ref "U1") (pin "G7") (pinfunction "EPHY_VCC_G7") (pintype "passive"))
      (node (ref "U1") (pin "H13") (pinfunction "VCC-IO_H13") (pintype "passive"))
      (node (ref "U1") (pin "H14") (pinfunction "VCC-IO_H14") (pintype "passive"))
      (node (ref "U1") (pin "H7") (pinfunction "VCC_PG_H7") (pintype "passive"))
      (node (ref "U1") (pin "J14") (pinfunction "VCC-IO_J14") (pintype "passive"))
      (node (ref "U1") (pin "J15") (pinfunction "VCC_PD_J15") (pintype "passive"))
      (node (ref "U1") (pin "J6") (pinfunction "HVCC_J6") (pintype "passive"))
    )
    (net (code "45") (name "VDD_AV") (class "Default")
      (node (ref "C2") (pin "2") (pinfunction "2_2") (pintype "passive"))
      (node (ref "C3") (pin "2") (pinfunction "2_2") (pintype "passive"))
      (node (ref "U1") (pin "G9") (pinfunction "V33_TV_G9") (pintype "passive"))
    )
    (net (code "46") (name "VDD_AVCC") (class "Default")
      (node (ref "R1") (pin "1") (pinfunction "1_1") (pintype "passive"))
      (node (ref "U1") (pin "K6") (pinfunction "VCC_RTC_K6") (pintype "passive"))
      (node (ref "U1") (pin "N3") (pinfunction "VCC_PLL_N3") (pintype "passive"))
      (node (ref "U1") (pin "V3") (pinfunction "AVCC_V3") (pintype "passive"))
    )
    (net (code "47") (name "VDD_CPUFB") (class "Default")
      (node (ref "R8") (pin "1") (pinfunction "1_1") (pintype "passive"))
      (node (ref "U1") (pin "T10") (pinfunction "VDD-CPUFB_T10") (pintype "passive"))
    )
    (net (code "48") (name "VDD_CPUS") (class "Default")
      (node (ref "C20") (pin "1") (pinfunction "1_1") (pintype "passive"))
      (node (ref "C21") (pin "1") (pinfunction "1_1") (pintype "passive"))
      (node (ref "U1") (pin "J7") (pinfunction "VDD_CPUS_J7") (pintype "passive"))
      (node (ref "U1") (pin "J8") (pinfunction "VDD_CPUS_J8") (pintype "passive"))
    )
    (net (code "49") (name "VDD_CPUX") (class "Default")
      (node (ref "C5") (pin "1") (pinfunction "1_1") (pintype "passive"))
      (node (ref "C6") (pin "1") (pinfunction "1_1") (pintype "passive"))
      (node (ref "C7") (pin "1") (pinfunction "1_1") (pintype "passive"))
      (node (ref "R8") (pin "2") (pinfunction "2_2") (pintype "passive"))
      (node (ref "U1") (pin "N8") (pinfunction "VDD_CPUX_N8") (pintype "passive"))
      (node (ref "U1") (pin "P6") (pinfunction "VDD_CPUX_P6") (pintype "passive"))
      (node (ref "U1") (pin "P7") (pinfunction "VDD_CPUX_P7") (pintype "passive"))
      (node (ref "U1") (pin "P8") (pinfunction "VDD_CPUX_P8") (pintype "passive"))
      (node (ref "U1") (pin "P9") (pinfunction "VDD_CPUX_P9") (pintype "passive"))
      (node (ref "U1") (pin "R6") (pinfunction "VDD_CPUX_R6") (pintype "passive"))
      (node (ref "U1") (pin "R7") (pinfunction "VDD_CPUX_R7") (pintype "passive"))
      (node (ref "U1") (pin "R8") (pinfunction "VDD_CPUX_R8") (pintype "passive"))
      (node (ref "U1") (pin "T6") (pinfunction "VDD_CPUX_T6") (pintype "passive"))
      (node (ref "U1") (pin "T7") (pinfunction "VDD_CPUX_T7") (pintype "passive"))
      (node (ref "U1") (pin "T8") (pinfunction "VDD_CPUX_T8") (pintype "passive"))
      (node (ref "U1") (pin "U6") (pinfunction "VDD_CPUX_U6") (pintype "passive"))
      (node (ref "U1") (pin "U9") (pinfunction "VDD_CPUX_U9") (pintype "passive"))
    )
    (net (code "50") (name "VDD_EFUSSEBP") (class "Default")
      (node (ref "C14") (pin "2") (pinfunction "2_2") (pintype "passive"))
      (node (ref "U1") (pin "H11") (pinfunction "VDD_EFUSEEBP_H11") (pintype "passive"))
    )
    (net (code "51") (name "VDD_EPHY") (class "Default")
      (node (ref "U1") (pin "F8") (pinfunction "EPHY_VDD_F8") (pintype "passive"))
    )
    (net (code "52") (name "VDD_SYS") (class "Default")
      (node (ref "C17") (pin "1") (pinfunction "1_1") (pintype "passive"))
      (node (ref "C18") (pin "1") (pinfunction "1_1") (pintype "passive"))
      (node (ref "C19") (pin "1") (pinfunction "1_1") (pintype "passive"))
      (node (ref "U1") (pin "H10") (pinfunction "VDD-SYS_H10") (pintype "passive"))
      (node (ref "U1") (pin "J10") (pinfunction "VDD-SYS_J10") (pintype "passive"))
      (node (ref "U1") (pin "J11") (pinfunction "VDD-SYS_J11") (pintype "passive"))
      (node (ref "U1") (pin "J12") (pinfunction "VDD-SYS_J12") (pintype "passive"))
      (node (ref "U1") (pin "K10") (pinfunction "VDD-SYS_K10") (pintype "passive"))
      (node (ref "U1") (pin "K11") (pinfunction "VDD-SYS_K11") (pintype "passive"))
      (node (ref "U1") (pin "K12") (pinfunction "VDD-SYS_K12") (pintype "passive"))
      (node (ref "U1") (pin "L10") (pinfunction "VDD-SYS_L10") (pintype "passive"))
      (node (ref "U1") (pin "L11") (pinfunction "VDD-SYS_L11") (pintype "passive"))
      (node (ref "U1") (pin "L12") (pinfunction "VDD-SYS_L12") (pintype "passive"))
      (node (ref "U1") (pin "L13") (pinfunction "VDD-SYS_L13") (pintype "passive"))
      (node (ref "U1") (pin "L14") (pinfunction "VDD-SYS_L14") (pintype "passive"))
    )
    (net (code "53") (name "unconnected-(U1A-JTAG-SEL0-PadA1)") (class "Default")
      (node (ref "U1") (pin "A1") (pinfunction "JTAG-SEL0_A1") (pintype "passive+no_connect"))
    )
    (net (code "54") (name "unconnected-(U1A-JTAG-SEL1-PadB2)") (class "Default")
      (node (ref "U1") (pin "B2") (pinfunction "JTAG-SEL1_B2") (pintype "passive+no_connect"))
    )
    (net (code "55") (name "unconnected-(U1A-NC-PadK4)") (class "Default")
      (node (ref "U1") (pin "K4") (pinfunction "NC_K4") (pintype "passive+no_connect"))
    )
    (net (code "56") (name "unconnected-(U1A-X32KFOUT-PadP3)") (class "Default")
      (node (ref "U1") (pin "P3") (pinfunction "X32KFOUT_P3") (pintype "passive+no_connect"))
    )
    (net (code "57") (name "unconnected-(U1A-X32KIN-PadV5)") (class "Default")
      (node (ref "U1") (pin "V5") (pinfunction "X32KIN_V5") (pintype "passive+no_connect"))
    )
    (net (code "58") (name "unconnected-(U1A-X32KOUT-PadU4)") (class "Default")
      (node (ref "U1") (pin "U4") (pinfunction "X32KOUT_U4") (pintype "passive+no_connect"))
    )
    (net (code "59") (name "unconnected-(X1-Pad2)") (class "Default")
      (node (ref "X1") (pin "2") (pinfunction "2_2") (pintype "passive+no_connect"))
    )
    (net (code "60") (name "unconnected-(X1-Pad4)") (class "Default")
      (node (ref "X1") (pin "4") (pinfunction "4_4") (pintype "passive+no_connect"))
    )
  )
)
